# DoorBell.net
KiCad netlist of a schematic drawn in EAGLE
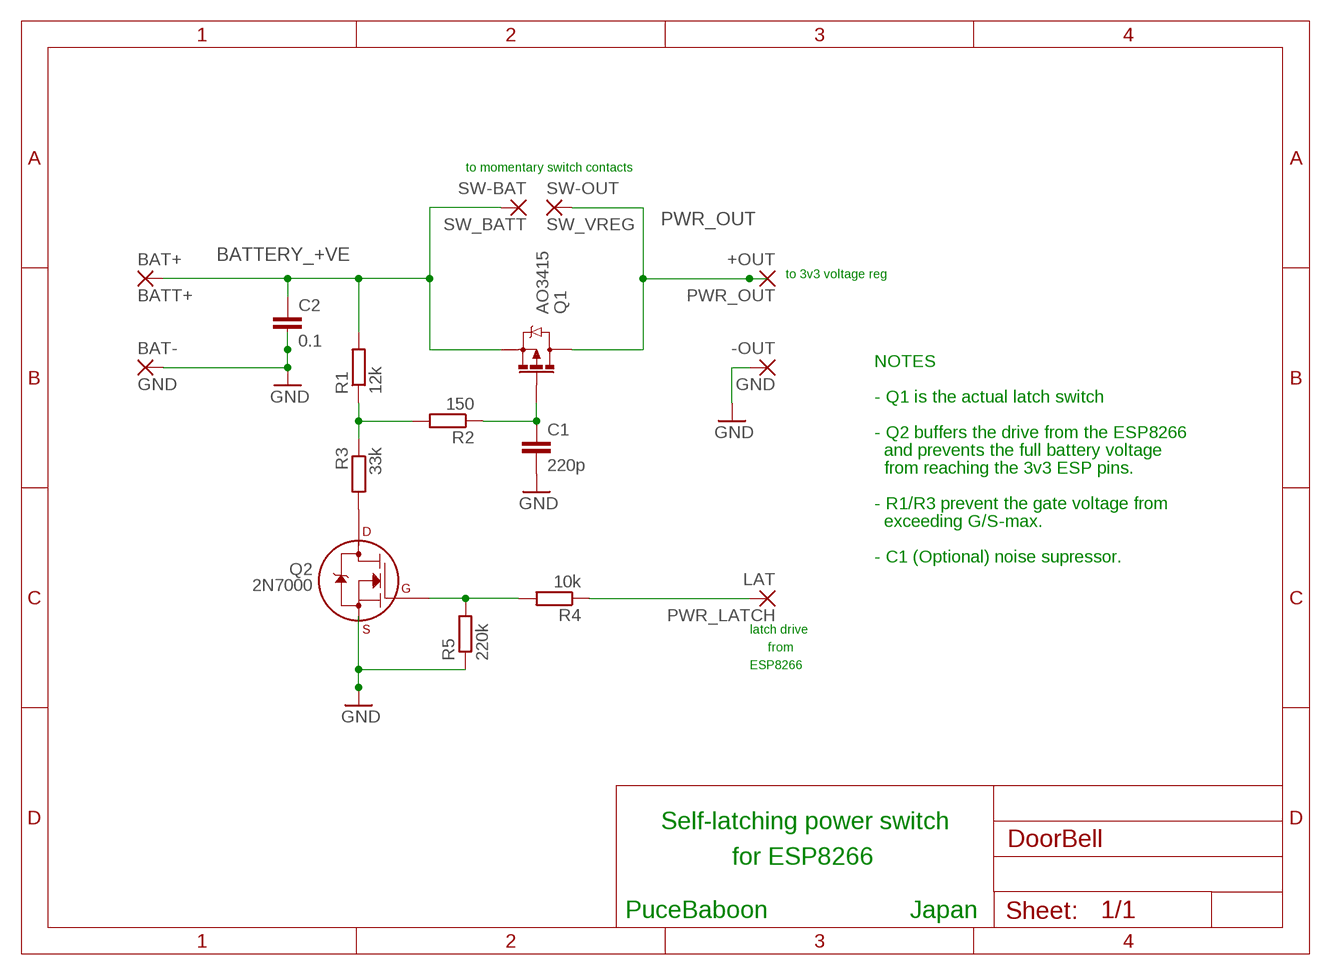
[diagram p0: schematic, sheet 1]

(export (version "E")
  (design (tool "Eeschema 10.0.6"))
  (components
    (comp (ref "+OUT")
      (value "PWR_OUT")
      (footprint "eagle-import:2,54_0,9")
      (libsource (lib "eagle-import") (part "2,54/0,9"))
    )
    (comp (ref "-OUT")
      (value "GND")
      (footprint "eagle-import:2,54_0,9")
      (libsource (lib "eagle-import") (part "2,54/0,9"))
    )
    (comp (ref "BAT+")
      (value "BATT+")
      (footprint "eagle-import:2,54_0,9")
      (libsource (lib "eagle-import") (part "2,54/0,9"))
    )
    (comp (ref "BAT-")
      (value "GND")
      (footprint "eagle-import:2,54_0,9")
      (libsource (lib "eagle-import") (part "2,54/0,9"))
    )
    (comp (ref "C1")
      (value "220p")
      (footprint "eagle-import:C025-025X050")
      (libsource (lib "eagle-import") (part "C-EU025-025X050"))
    )
    (comp (ref "C2")
      (value "0.1")
      (footprint "eagle-import:C025-025X050")
      (libsource (lib "eagle-import") (part "C-EU025-025X050"))
    )
    (comp (ref "LAT")
      (value "PWR_LATCH")
      (footprint "eagle-import:2,54_0,9")
      (libsource (lib "eagle-import") (part "2,54/0,9"))
    )
    (comp (ref "Q1")
      (value "AO3415")
      (footprint "eagle-import:SOT23-3")
      (libsource (lib "eagle-import") (part "MOSFET-PCHANNEL_SOT23-3"))
    )
    (comp (ref "Q2")
      (value "2N7000")
      (footprint "eagle-import:TO-92")
      (libsource (lib "eagle-import") (part "2N700_TO920"))
    )
    (comp (ref "R1")
      (value "12k")
      (footprint "eagle-import:0204_7")
      (libsource (lib "eagle-import") (part "R-EU_0204/7"))
    )
    (comp (ref "R2")
      (value "150")
      (footprint "eagle-import:0204_7")
      (libsource (lib "eagle-import") (part "R-EU_0204/7"))
    )
    (comp (ref "R3")
      (value "33k")
      (footprint "eagle-import:0204_7")
      (libsource (lib "eagle-import") (part "R-EU_0204/7"))
    )
    (comp (ref "R4")
      (value "10k")
      (footprint "eagle-import:0204_7")
      (libsource (lib "eagle-import") (part "R-EU_0204/7"))
    )
    (comp (ref "R5")
      (value "220k")
      (footprint "eagle-import:0204_7")
      (libsource (lib "eagle-import") (part "R-EU_0204/7"))
    )
    (comp (ref "SW-BAT")
      (value "SW_BATT")
      (footprint "eagle-import:2,54_0,9")
      (libsource (lib "eagle-import") (part "2,54/0,9"))
    )
    (comp (ref "SW-OUT")
      (value "SW_VREG")
      (footprint "eagle-import:2,54_0,9")
      (libsource (lib "eagle-import") (part "2,54/0,9"))
    )
  )
  (nets
    (net (code "1") (name "/BATTERY_+VE") (class "Default")
      (node (ref "BAT+") (pin "1") (pinfunction "P_1") (pintype "passive"))
      (node (ref "C2") (pin "1") (pinfunction "1_1") (pintype "passive"))
      (node (ref "Q1") (pin "2") (pinfunction "S_2") (pintype "passive"))
      (node (ref "R1") (pin "2") (pinfunction "2_2") (pintype "passive"))
      (node (ref "SW-BAT") (pin "1") (pinfunction "P_1") (pintype "passive"))
    )
    (net (code "2") (name "/PWR_OUT") (class "Default")
      (node (ref "+OUT") (pin "1") (pinfunction "P_1") (pintype "passive"))
      (node (ref "Q1") (pin "3") (pinfunction "D_3") (pintype "passive"))
      (node (ref "SW-OUT") (pin "1") (pinfunction "P_1") (pintype "passive"))
    )
    (net (code "3") (name "GND") (class "Default")
      (node (ref "-OUT") (pin "1") (pinfunction "P_1") (pintype "passive"))
      (node (ref "BAT-") (pin "1") (pinfunction "P_1") (pintype "passive"))
      (node (ref "C1") (pin "2") (pinfunction "2_2") (pintype "passive"))
      (node (ref "C2") (pin "2") (pinfunction "2_2") (pintype "passive"))
      (node (ref "Q2") (pin "1") (pinfunction "S_1") (pintype "bidirectional"))
      (node (ref "R5") (pin "1") (pinfunction "1_1") (pintype "passive"))
    )
    (net (code "4") (name "Net-(LAT-P)") (class "Default")
      (node (ref "LAT") (pin "1") (pinfunction "P_1") (pintype "passive"))
      (node (ref "R4") (pin "1") (pinfunction "1_1") (pintype "passive"))
    )
    (net (code "5") (name "Net-(Q1-G)") (class "Default")
      (node (ref "C1") (pin "1") (pinfunction "1_1") (pintype "passive"))
      (node (ref "Q1") (pin "1") (pinfunction "G_1") (pintype "passive"))
      (node (ref "R2") (pin "1") (pinfunction "1_1") (pintype "passive"))
    )
    (net (code "6") (name "Net-(Q2-D)") (class "Default")
      (node (ref "Q2") (pin "3") (pinfunction "D_3") (pintype "bidirectional"))
      (node (ref "R3") (pin "2") (pinfunction "2_2") (pintype "passive"))
    )
    (net (code "7") (name "Net-(Q2-G)") (class "Default")
      (node (ref "Q2") (pin "2") (pinfunction "G_2") (pintype "tri_state"))
      (node (ref "R4") (pin "2") (pinfunction "2_2") (pintype "passive"))
      (node (ref "R5") (pin "2") (pinfunction "2_2") (pintype "passive"))
    )
    (net (code "8") (name "Net-(R1-Pad1)") (class "Default")
      (node (ref "R1") (pin "1") (pinfunction "1_1") (pintype "passive"))
      (node (ref "R2") (pin "2") (pinfunction "2_2") (pintype "passive"))
      (node (ref "R3") (pin "1") (pinfunction "1_1") (pintype "passive"))
    )
  )
)
